# opaq_n1.net
KiCad netlist of a schematic drawn in EAGLE
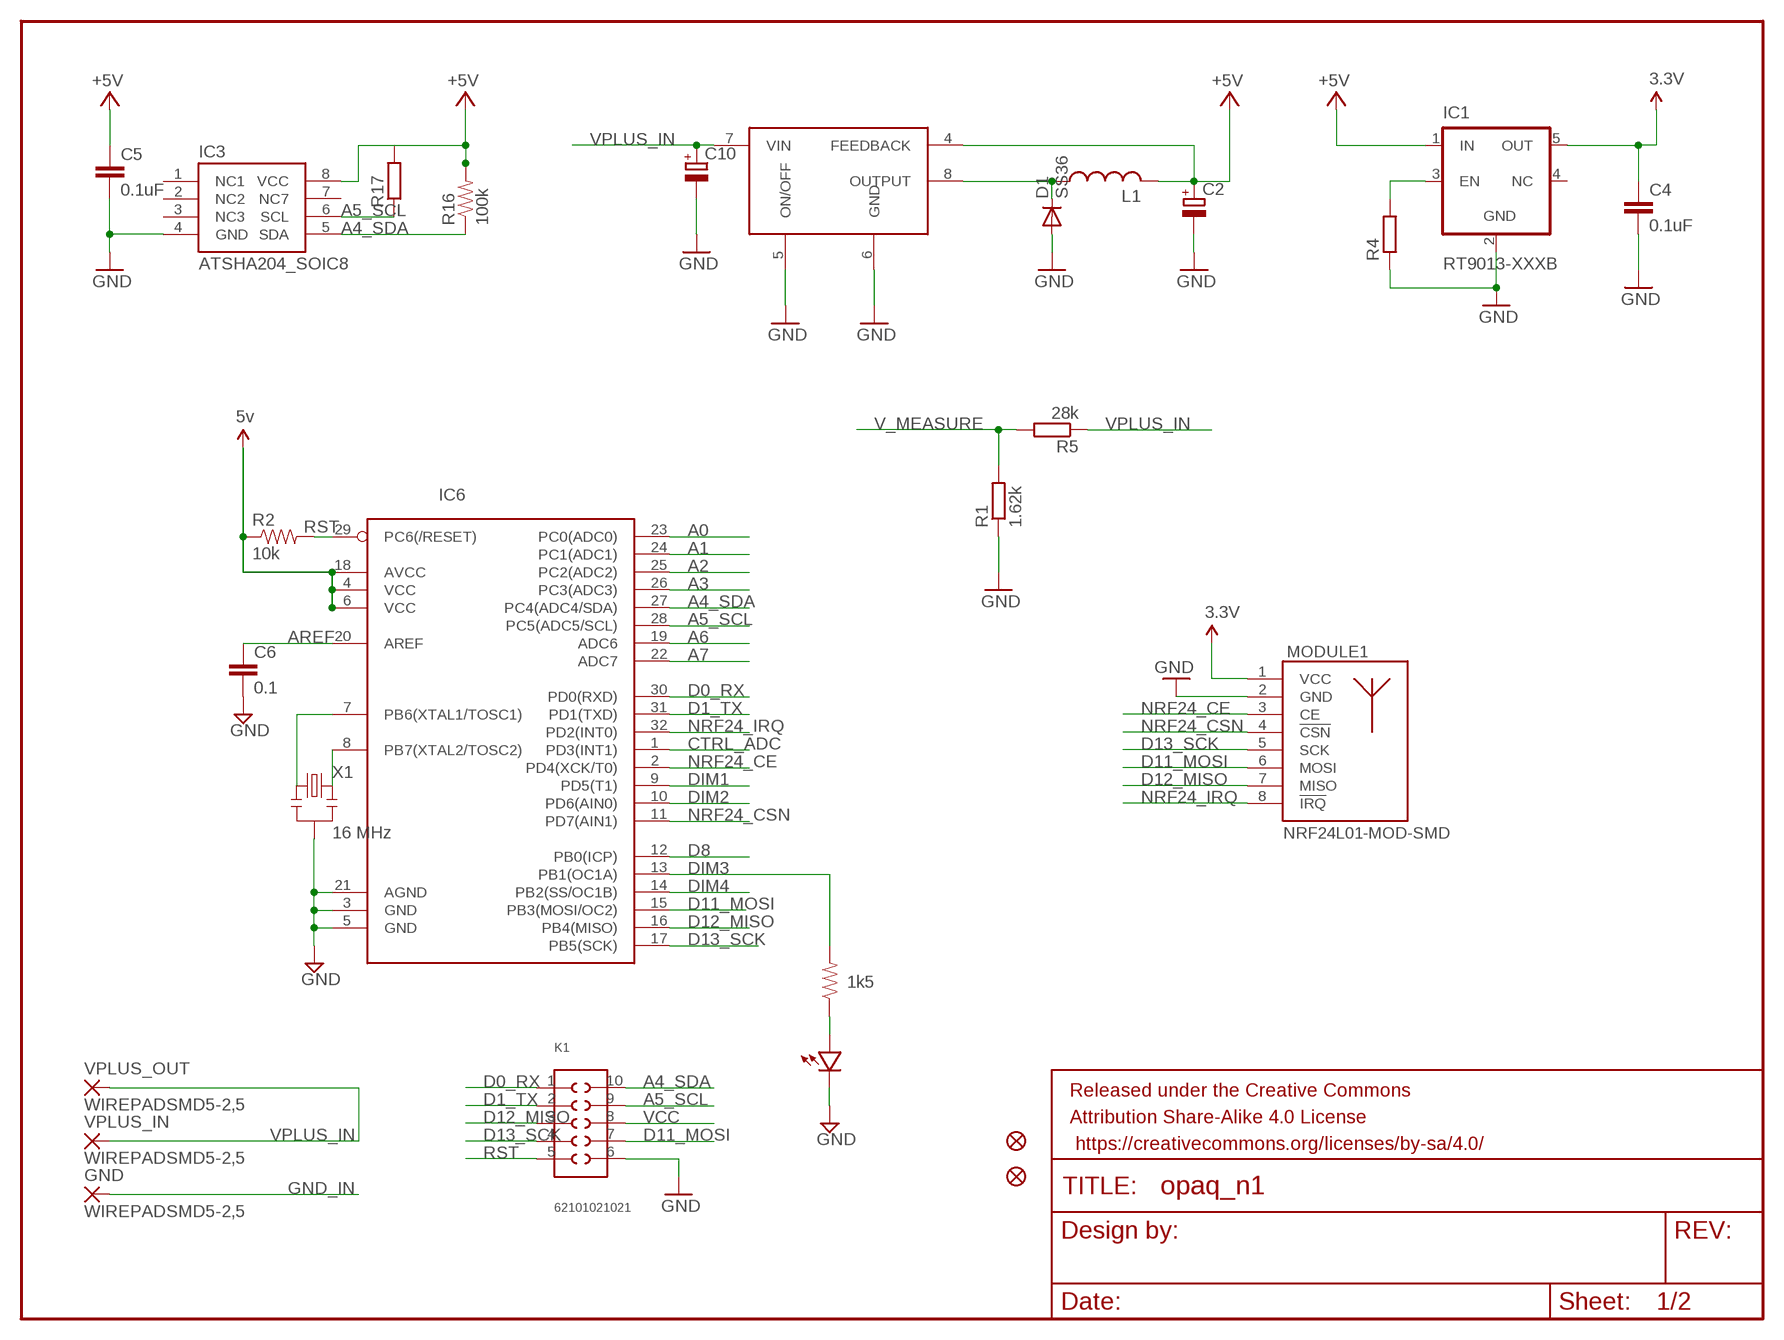
[diagram p0: schematic, sheet 1]
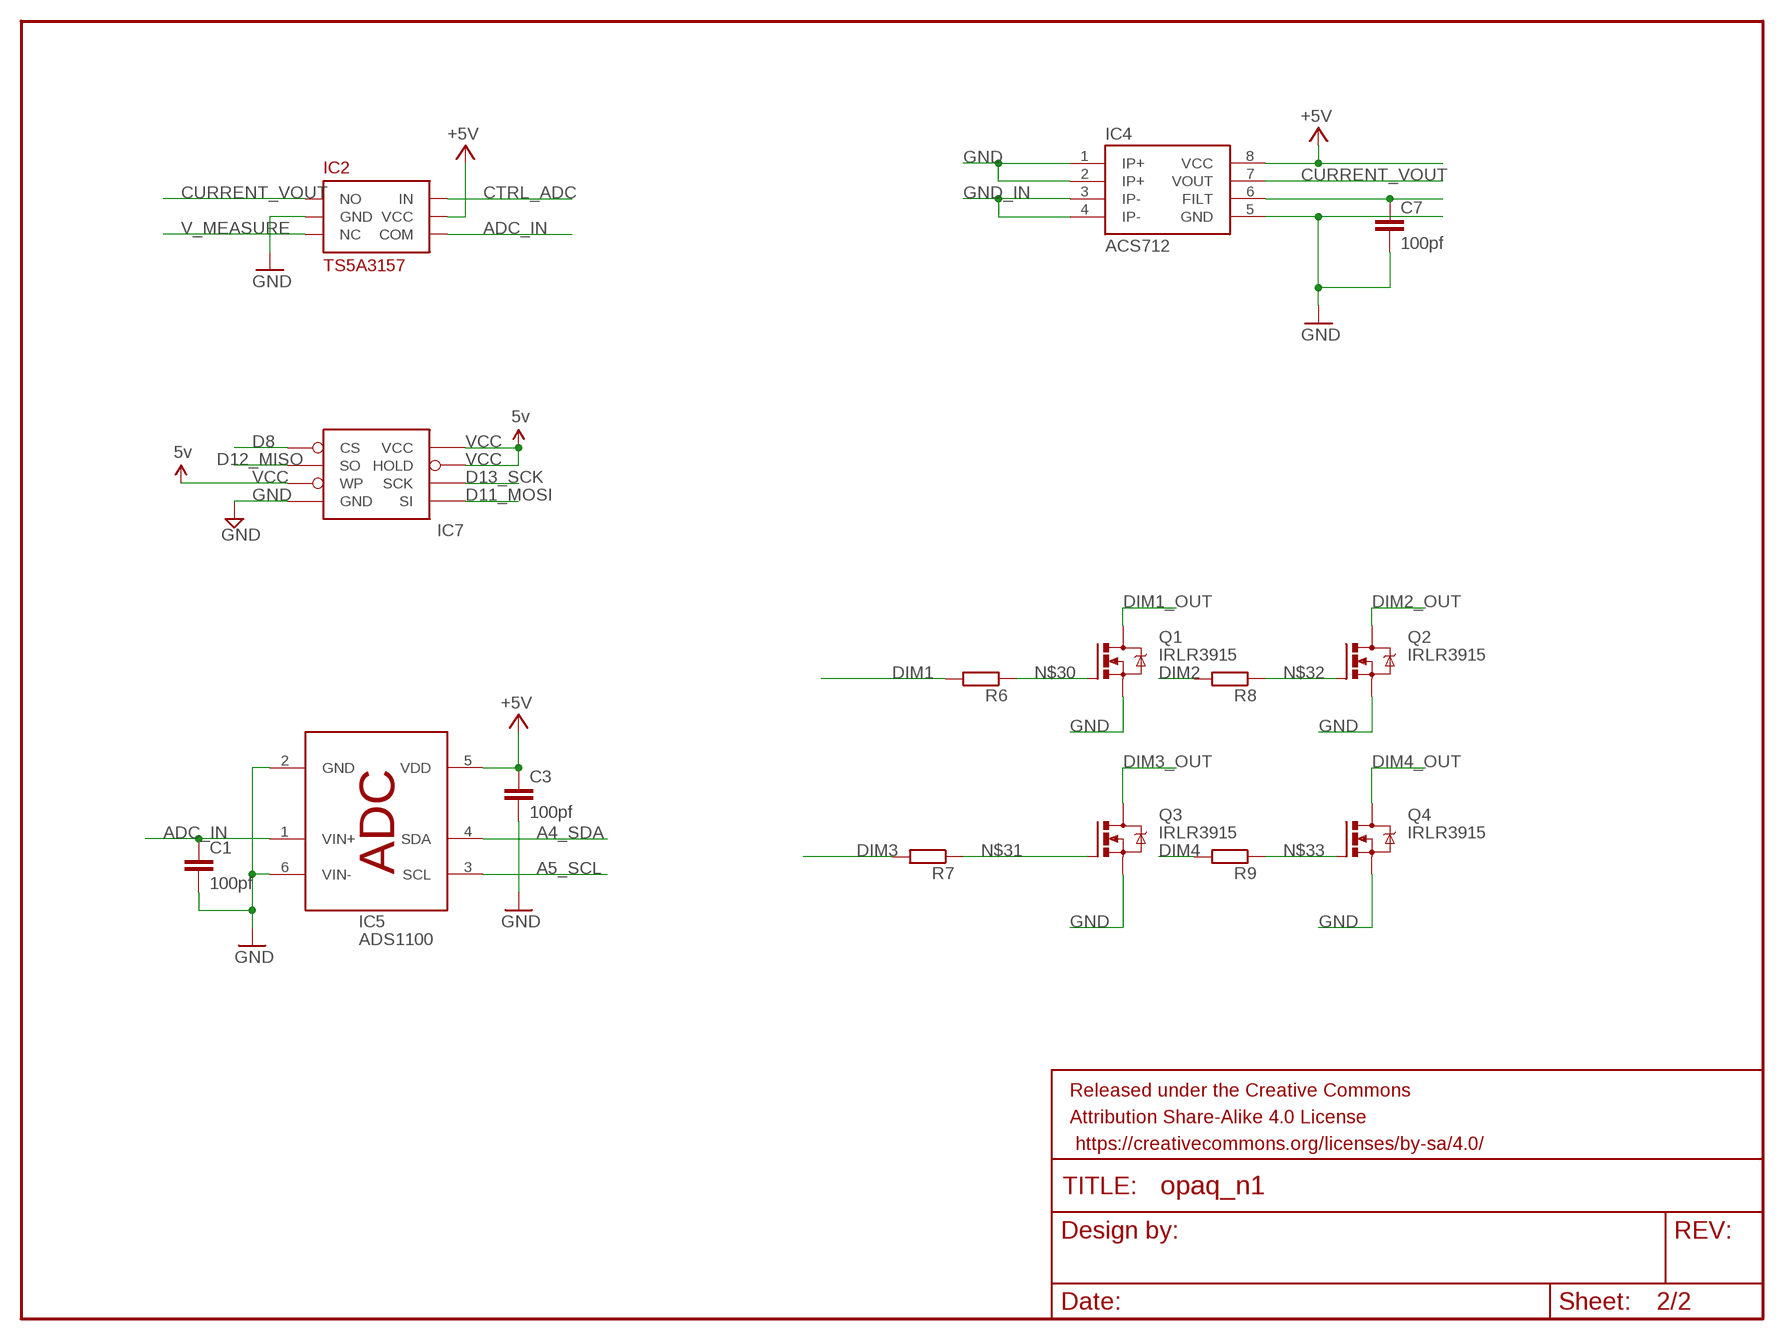
[diagram p1: schematic, sheet 2]

(export (version "E")
  (design (tool "Eeschema 10.0.6"))
  (components
    (comp (ref "C2")
      (value "CPOL-EUC/6032-28R")
      (footprint "eagle-import:C_6032-28R")
      (libsource (lib "eagle-import") (part "CPOL-EUC/6032-28R"))
    )
    (comp (ref "C4")
      (value "0.1uF")
      (footprint "eagle-import:0805")
      (libsource (lib "eagle-import") (part "SparkFun-Passives_CAP0805"))
    )
    (comp (ref "C5")
      (value "0.1uF")
      (footprint "eagle-import:0805")
      (libsource (lib "eagle-import") (part "SparkFun-Passives_CAP0805"))
    )
    (comp (ref "C6")
      (value "0.1")
      (footprint "eagle-import:0603-CAP")
      (libsource (lib "eagle-import") (part "CAP0603-CAP"))
    )
    (comp (ref "C10")
      (value "CPOL-EUD/7343-31R")
      (footprint "eagle-import:D_7343-31R")
      (libsource (lib "eagle-import") (part "CPOL-EUD/7343-31R"))
    )
    (comp (ref "D1")
      (value "SS36")
      (footprint "eagle-import:SMA-DIODE")
      (libsource (lib "eagle-import") (part "DIODESMA"))
    )
    (comp (ref "DIM")
      (value "LED0603")
      (footprint "eagle-import:0603-LED")
      (libsource (lib "eagle-import") (part "LED0603"))
    )
    (comp (ref "FRAME1")
      (value "FRAME-LETTER")
      (footprint "eagle-import:CREATIVE_COMMONS")
      (libsource (lib "eagle-import") (part "FRAME-LETTER"))
    )
    (comp (ref "GND")
      (value "WIREPADSMD5-2,5")
      (footprint "eagle-import:5-2,5")
      (libsource (lib "eagle-import") (part "WIREPADSMD5-2,5"))
    )
    (comp (ref "IC1")
      (value "RT9013-XXXB")
      (footprint "eagle-import:SOT23-5")
      (libsource (lib "eagle-import") (part "RT9013-XXXB"))
    )
    (comp (ref "IC3")
      (value "ATSHA204_SOIC8")
      (footprint "eagle-import:SOIC8")
      (libsource (lib "eagle-import") (part "ATSHA204_SOIC8"))
    )
    (comp (ref "IC6")
      (value "ATMega-328")
      (footprint "eagle-import:MLF32")
      (libsource (lib "eagle-import") (part "ATMEGA168/328MLF"))
    )
    (comp (ref "IC8")
      (value "LM2594HV")
      (footprint "eagle-import:SO08")
      (libsource (lib "eagle-import") (part "LM2594"))
    )
    (comp (ref "JP1")
      (value "FIDUCIAL1X2.5")
      (footprint "eagle-import:FIDUCIAL-1X2.5")
      (libsource (lib "eagle-import") (part "FIDUCIAL1X2.5"))
    )
    (comp (ref "JP2")
      (value "FIDUCIAL1X2.5")
      (footprint "eagle-import:FIDUCIAL-1X2.5")
      (libsource (lib "eagle-import") (part "FIDUCIAL1X2.5"))
    )
    (comp (ref "K1")
      (value "62101021021")
      (footprint "eagle-import:62101021021")
      (libsource (lib "eagle-import") (part "62101021021"))
    )
    (comp (ref "L1")
      (value "NR6045")
      (footprint "eagle-import:2525")
      (libsource (lib "eagle-import") (part "NR6045"))
    )
    (comp (ref "MODULE1")
      (value "NRF24L01-MOD-SMD")
      (footprint "eagle-import:SMD8-MODULE")
      (libsource (lib "eagle-import") (part "NRF24L01-MOD-SMD"))
    )
    (comp (ref "R1")
      (value "1.62k")
      (footprint "eagle-import:0805")
      (libsource (lib "eagle-import") (part "R-EU_R0805"))
    )
    (comp (ref "R2")
      (value "10k")
      (footprint "eagle-import:0603-RES")
      (libsource (lib "eagle-import") (part "RESISTOR0603-RES"))
    )
    (comp (ref "R3")
      (value "1k5")
      (footprint "eagle-import:0603-RES")
      (libsource (lib "eagle-import") (part "RESISTOR0603-RES"))
    )
    (comp (ref "R4")
      (value "R-EU_R0805")
      (footprint "eagle-import:0805")
      (libsource (lib "eagle-import") (part "R-EU_R0805"))
    )
    (comp (ref "R5")
      (value "28k")
      (footprint "eagle-import:0805")
      (libsource (lib "eagle-import") (part "R-EU_R0805"))
    )
    (comp (ref "R16")
      (value "100k")
      (footprint "eagle-import:0805")
      (libsource (lib "eagle-import") (part "SparkFun-Passives_RESISTOR0805-RES"))
    )
    (comp (ref "R17")
      (value "R-EU_R0805")
      (footprint "eagle-import:0805")
      (libsource (lib "eagle-import") (part "R-EU_R0805"))
    )
    (comp (ref "VPLUS_IN")
      (value "WIREPADSMD5-2,5")
      (footprint "eagle-import:5-2,5")
      (libsource (lib "eagle-import") (part "WIREPADSMD5-2,5"))
    )
    (comp (ref "VPLUS_OUT")
      (value "WIREPADSMD5-2,5")
      (footprint "eagle-import:5-2,5")
      (libsource (lib "eagle-import") (part "WIREPADSMD5-2,5"))
    )
    (comp (ref "X1")
      (value "16 MHz")
      (footprint "eagle-import:RESONATOR-SMD")
      (libsource (lib "eagle-import") (part "RESONATORSMD"))
    )
    (comp (ref "C1")
      (value "100pf")
      (footprint "eagle-import:0402-CAP")
      (libsource (lib "eagle-import") (part "SparkFun-Passives_CAP0402-CAP"))
    )
    (comp (ref "C3")
      (value "100pf")
      (footprint "eagle-import:0402-CAP")
      (libsource (lib "eagle-import") (part "SparkFun-Passives_CAP0402-CAP"))
    )
    (comp (ref "C7")
      (value "100pf")
      (footprint "eagle-import:0402-CAP")
      (libsource (lib "eagle-import") (part "SparkFun-Passives_CAP0402-CAP"))
    )
    (comp (ref "FRAME2")
      (value "FRAME-LETTERNO_PACKAGE")
      (footprint "eagle-import:DUMMY")
      (fields (field (name "DESIGNER") "Nobody"))
      (libsource (lib "eagle-import") (part "FRAME-LETTERNO_PACKAGE"))
    )
    (comp (ref "IC2")
      (value "TS5A3157")
      (footprint "eagle-import:SOT23-6")
      (libsource (lib "eagle-import") (part "TS5A3157"))
    )
    (comp (ref "IC4")
      (value "ACS712")
      (footprint "eagle-import:SO08")
      (libsource (lib "eagle-import") (part "ACS712"))
    )
    (comp (ref "IC5")
      (value "ADS1100")
      (footprint "eagle-import:SOT23-6")
      (fields (field (name "MF") "TI"))
      (libsource (lib "eagle-import") (part "ADS1100"))
    )
    (comp (ref "IC7")
      (value "AT25F512BWIDE_5.3MM")
      (footprint "eagle-import:SO08WIDE")
      (libsource (lib "eagle-import") (part "AT25F512BWIDE_5.3MM"))
    )
    (comp (ref "Q1")
      (value "IRLR3915")
      (footprint "eagle-import:D-PAK_TO252AA")
      (libsource (lib "eagle-import") (part "IRLR3915"))
    )
    (comp (ref "Q2")
      (value "IRLR3915")
      (footprint "eagle-import:D-PAK_TO252AA")
      (libsource (lib "eagle-import") (part "IRLR3915"))
    )
    (comp (ref "Q3")
      (value "IRLR3915")
      (footprint "eagle-import:D-PAK_TO252AA")
      (libsource (lib "eagle-import") (part "IRLR3915"))
    )
    (comp (ref "Q4")
      (value "IRLR3915")
      (footprint "eagle-import:D-PAK_TO252AA")
      (libsource (lib "eagle-import") (part "IRLR3915"))
    )
    (comp (ref "R6")
      (value "R-EU_R0805")
      (footprint "eagle-import:0805")
      (libsource (lib "eagle-import") (part "R-EU_R0805"))
    )
    (comp (ref "R7")
      (value "R-EU_R0805")
      (footprint "eagle-import:0805")
      (libsource (lib "eagle-import") (part "R-EU_R0805"))
    )
    (comp (ref "R8")
      (value "R-EU_R0805")
      (footprint "eagle-import:0805")
      (libsource (lib "eagle-import") (part "R-EU_R0805"))
    )
    (comp (ref "R9")
      (value "R-EU_R0805")
      (footprint "eagle-import:0805")
      (libsource (lib "eagle-import") (part "R-EU_R0805"))
    )
  )
  (nets
    (net (code "1") (name "+5V") (class "Default")
      (node (ref "C2") (pin "+") (pinfunction "+_+") (pintype "passive"))
      (node (ref "C3") (pin "1") (pinfunction "1_1") (pintype "passive"))
      (node (ref "C5") (pin "1") (pinfunction "1_1") (pintype "passive"))
      (node (ref "IC1") (pin "1") (pinfunction "IN_1") (pintype "input"))
      (node (ref "IC2") (pin "5") (pinfunction "VCC_5") (pintype "bidirectional"))
      (node (ref "IC3") (pin "8") (pinfunction "VCC_8") (pintype "power_in"))
      (node (ref "IC4") (pin "8") (pinfunction "VCC_8") (pintype "bidirectional"))
      (node (ref "IC5") (pin "5") (pinfunction "VDD_5") (pintype "power_in"))
      (node (ref "IC8") (pin "4") (pinfunction "FEEDBACK_4") (pintype "bidirectional"))
      (node (ref "L1") (pin "P$1") (pinfunction "P$1_P$1") (pintype "passive"))
      (node (ref "R16") (pin "2") (pinfunction "2_2") (pintype "passive"))
      (node (ref "R17") (pin "2") (pinfunction "2_2") (pintype "passive"))
    )
    (net (code "2") (name "3.3V") (class "Default")
      (node (ref "C4") (pin "1") (pinfunction "1_1") (pintype "passive"))
      (node (ref "IC1") (pin "5") (pinfunction "OUT_5") (pintype "passive"))
      (node (ref "MODULE1") (pin "1") (pinfunction "VCC_1") (pintype "power_in"))
    )
    (net (code "3") (name "A0") (class "Default")
      (node (ref "IC6") (pin "23") (pinfunction "PC0(ADC0)_23") (pintype "bidirectional"))
    )
    (net (code "4") (name "A1") (class "Default")
      (node (ref "IC6") (pin "24") (pinfunction "PC1(ADC1)_24") (pintype "bidirectional"))
    )
    (net (code "5") (name "A2") (class "Default")
      (node (ref "IC6") (pin "25") (pinfunction "PC2(ADC2)_25") (pintype "bidirectional"))
    )
    (net (code "6") (name "A3") (class "Default")
      (node (ref "IC6") (pin "26") (pinfunction "PC3(ADC3)_26") (pintype "bidirectional"))
    )
    (net (code "7") (name "A4_SDA") (class "Default")
      (node (ref "IC3") (pin "5") (pinfunction "SDA_5") (pintype "bidirectional"))
      (node (ref "IC5") (pin "4") (pinfunction "SDA_4") (pintype "bidirectional"))
      (node (ref "IC6") (pin "27") (pinfunction "PC4(ADC4/SDA)_27") (pintype "bidirectional"))
      (node (ref "K1") (pin "10") (pinfunction "10_10") (pintype "passive"))
      (node (ref "R16") (pin "1") (pinfunction "1_1") (pintype "passive"))
    )
    (net (code "8") (name "A5_SCL") (class "Default")
      (node (ref "IC3") (pin "6") (pinfunction "SCL_6") (pintype "bidirectional"))
      (node (ref "IC5") (pin "3") (pinfunction "SCL_3") (pintype "input"))
      (node (ref "IC6") (pin "28") (pinfunction "PC5(ADC5/SCL)_28") (pintype "bidirectional"))
      (node (ref "K1") (pin "9") (pinfunction "9_9") (pintype "passive"))
      (node (ref "R17") (pin "1") (pinfunction "1_1") (pintype "passive"))
    )
    (net (code "9") (name "A6") (class "Default")
      (node (ref "IC6") (pin "19") (pinfunction "ADC6_19") (pintype "bidirectional"))
    )
    (net (code "10") (name "A7") (class "Default")
      (node (ref "IC6") (pin "22") (pinfunction "ADC7_22") (pintype "bidirectional"))
    )
    (net (code "11") (name "ADC_IN") (class "Default")
      (node (ref "C1") (pin "1") (pinfunction "1_1") (pintype "passive"))
      (node (ref "IC2") (pin "4") (pinfunction "COM_4") (pintype "bidirectional"))
      (node (ref "IC5") (pin "1") (pinfunction "VIN+_1") (pintype "input"))
    )
    (net (code "12") (name "AREF") (class "Default")
      (node (ref "C6") (pin "1") (pinfunction "1_1") (pintype "passive"))
      (node (ref "IC6") (pin "20") (pinfunction "AREF_20") (pintype "bidirectional"))
    )
    (net (code "13") (name "CTRL_ADC") (class "Default")
      (node (ref "IC2") (pin "6") (pinfunction "IN_6") (pintype "bidirectional"))
      (node (ref "IC6") (pin "1") (pinfunction "PD3(INT1)_1") (pintype "bidirectional"))
    )
    (net (code "14") (name "CURRENT_VOUT") (class "Default")
      (node (ref "IC2") (pin "1") (pinfunction "NO_1") (pintype "bidirectional"))
      (node (ref "IC4") (pin "7") (pinfunction "VOUT_7") (pintype "bidirectional"))
    )
    (net (code "15") (name "D0_RX") (class "Default")
      (node (ref "IC6") (pin "30") (pinfunction "PD0(RXD)_30") (pintype "bidirectional"))
      (node (ref "K1") (pin "1") (pinfunction "1_1") (pintype "passive"))
    )
    (net (code "16") (name "D1_TX") (class "Default")
      (node (ref "IC6") (pin "31") (pinfunction "PD1(TXD)_31") (pintype "bidirectional"))
      (node (ref "K1") (pin "2") (pinfunction "2_2") (pintype "passive"))
    )
    (net (code "17") (name "D8") (class "Default")
      (node (ref "IC6") (pin "12") (pinfunction "PB0(ICP)_12") (pintype "bidirectional"))
      (node (ref "IC7") (pin "1") (pinfunction "CS_1") (pintype "bidirectional"))
    )
    (net (code "18") (name "D11_MOSI") (class "Default")
      (node (ref "IC6") (pin "15") (pinfunction "PB3(MOSI/OC2)_15") (pintype "bidirectional"))
      (node (ref "IC7") (pin "5") (pinfunction "SI_5") (pintype "bidirectional"))
      (node (ref "K1") (pin "7") (pinfunction "7_7") (pintype "passive"))
      (node (ref "MODULE1") (pin "6") (pinfunction "MOSI_6") (pintype "input"))
    )
    (net (code "19") (name "D12_MISO") (class "Default")
      (node (ref "IC6") (pin "16") (pinfunction "PB4(MISO)_16") (pintype "bidirectional"))
      (node (ref "IC7") (pin "2") (pinfunction "SO_2") (pintype "bidirectional"))
      (node (ref "K1") (pin "3") (pinfunction "3_3") (pintype "passive"))
      (node (ref "MODULE1") (pin "7") (pinfunction "MISO_7") (pintype "output"))
    )
    (net (code "20") (name "D13_SCK") (class "Default")
      (node (ref "IC6") (pin "17") (pinfunction "PB5(SCK)_17") (pintype "bidirectional"))
      (node (ref "IC7") (pin "6") (pinfunction "SCK_6") (pintype "bidirectional"))
      (node (ref "K1") (pin "4") (pinfunction "4_4") (pintype "passive"))
      (node (ref "MODULE1") (pin "5") (pinfunction "SCK_5") (pintype "input"))
    )
    (net (code "21") (name "DIM1") (class "Default")
      (node (ref "IC6") (pin "9") (pinfunction "PD5(T1)_9") (pintype "bidirectional"))
      (node (ref "R6") (pin "2") (pinfunction "2_2") (pintype "passive"))
    )
    (net (code "22") (name "DIM1_OUT") (class "Default")
      (node (ref "Q1") (pin "4") (pinfunction "D_4") (pintype "passive"))
    )
    (net (code "23") (name "DIM2") (class "Default")
      (node (ref "IC6") (pin "10") (pinfunction "PD6(AIN0)_10") (pintype "bidirectional"))
      (node (ref "R8") (pin "2") (pinfunction "2_2") (pintype "passive"))
    )
    (net (code "24") (name "DIM2_OUT") (class "Default")
      (node (ref "Q2") (pin "4") (pinfunction "D_4") (pintype "passive"))
    )
    (net (code "25") (name "DIM3") (class "Default")
      (node (ref "IC6") (pin "13") (pinfunction "PB1(OC1A)_13") (pintype "bidirectional"))
      (node (ref "R3") (pin "2") (pinfunction "2_2") (pintype "passive"))
      (node (ref "R7") (pin "2") (pinfunction "2_2") (pintype "passive"))
    )
    (net (code "26") (name "DIM3_OUT") (class "Default")
      (node (ref "Q3") (pin "4") (pinfunction "D_4") (pintype "passive"))
    )
    (net (code "27") (name "DIM4") (class "Default")
      (node (ref "IC6") (pin "14") (pinfunction "PB2(SS/OC1B)_14") (pintype "bidirectional"))
      (node (ref "R9") (pin "2") (pinfunction "2_2") (pintype "passive"))
    )
    (net (code "28") (name "DIM4_OUT") (class "Default")
      (node (ref "Q4") (pin "4") (pinfunction "D_4") (pintype "passive"))
    )
    (net (code "29") (name "GND") (class "Default")
      (node (ref "C1") (pin "2") (pinfunction "2_2") (pintype "passive"))
      (node (ref "C10") (pin "-") (pinfunction "-_-") (pintype "passive"))
      (node (ref "C2") (pin "-") (pinfunction "-_-") (pintype "passive"))
      (node (ref "C3") (pin "2") (pinfunction "2_2") (pintype "passive"))
      (node (ref "C4") (pin "2") (pinfunction "2_2") (pintype "passive"))
      (node (ref "C5") (pin "2") (pinfunction "2_2") (pintype "passive"))
      (node (ref "C6") (pin "2") (pinfunction "2_2") (pintype "passive"))
      (node (ref "C7") (pin "2") (pinfunction "2_2") (pintype "passive"))
      (node (ref "D1") (pin "A") (pinfunction "A_A") (pintype "passive"))
      (node (ref "DIM") (pin "MINUS") (pinfunction "MINUS_MINUS") (pintype "passive"))
      (node (ref "IC1") (pin "2") (pinfunction "GND_2") (pintype "power_in"))
      (node (ref "IC2") (pin "2") (pinfunction "GND_2") (pintype "bidirectional"))
      (node (ref "IC3") (pin "4") (pinfunction "GND_4") (pintype "power_in"))
      (node (ref "IC4") (pin "1") (pinfunction "IP+_1") (pintype "bidirectional"))
      (node (ref "IC4") (pin "2") (pinfunction "IP+_2") (pintype "bidirectional"))
      (node (ref "IC4") (pin "5") (pinfunction "GND_5") (pintype "bidirectional"))
      (node (ref "IC5") (pin "2") (pinfunction "GND_2") (pintype "power_in"))
      (node (ref "IC5") (pin "6") (pinfunction "VIN-_6") (pintype "input"))
      (node (ref "IC6") (pin "21") (pinfunction "AGND_21") (pintype "bidirectional"))
      (node (ref "IC6") (pin "3") (pinfunction "GND_3") (pintype "bidirectional"))
      (node (ref "IC6") (pin "5") (pinfunction "GND_5") (pintype "bidirectional"))
      (node (ref "IC7") (pin "4") (pinfunction "GND_4") (pintype "bidirectional"))
      (node (ref "IC8") (pin "5") (pinfunction "ON/OFF_5") (pintype "bidirectional"))
      (node (ref "IC8") (pin "6") (pinfunction "GND_6") (pintype "bidirectional"))
      (node (ref "K1") (pin "6") (pinfunction "6_6") (pintype "passive"))
      (node (ref "MODULE1") (pin "2") (pinfunction "GND_2") (pintype "power_in"))
      (node (ref "Q1") (pin "3") (pinfunction "S_3") (pintype "passive"))
      (node (ref "Q2") (pin "3") (pinfunction "S_3") (pintype "passive"))
      (node (ref "Q3") (pin "3") (pinfunction "S_3") (pintype "passive"))
      (node (ref "Q4") (pin "3") (pinfunction "S_3") (pintype "passive"))
      (node (ref "R1") (pin "1") (pinfunction "1_1") (pintype "passive"))
      (node (ref "R4") (pin "1") (pinfunction "1_1") (pintype "passive"))
      (node (ref "X1") (pin "2") (pinfunction "2_2") (pintype "passive"))
    )
    (net (code "30") (name "GND_IN") (class "Default")
      (node (ref "GND") (pin "1") (pinfunction "P_1") (pintype "passive"))
      (node (ref "IC4") (pin "3") (pinfunction "IP-_3") (pintype "bidirectional"))
      (node (ref "IC4") (pin "4") (pinfunction "IP-_4") (pintype "bidirectional"))
    )
    (net (code "31") (name "N$30") (class "Default")
      (node (ref "Q1") (pin "1") (pinfunction "G_1") (pintype "passive"))
      (node (ref "R6") (pin "1") (pinfunction "1_1") (pintype "passive"))
    )
    (net (code "32") (name "N$31") (class "Default")
      (node (ref "Q3") (pin "1") (pinfunction "G_1") (pintype "passive"))
      (node (ref "R7") (pin "1") (pinfunction "1_1") (pintype "passive"))
    )
    (net (code "33") (name "N$32") (class "Default")
      (node (ref "Q2") (pin "1") (pinfunction "G_1") (pintype "passive"))
      (node (ref "R8") (pin "1") (pinfunction "1_1") (pintype "passive"))
    )
    (net (code "34") (name "N$33") (class "Default")
      (node (ref "Q4") (pin "1") (pinfunction "G_1") (pintype "passive"))
      (node (ref "R9") (pin "1") (pinfunction "1_1") (pintype "passive"))
    )
    (net (code "35") (name "NRF24_CE") (class "Default")
      (node (ref "IC6") (pin "2") (pinfunction "PD4(XCK/T0)_2") (pintype "bidirectional"))
      (node (ref "MODULE1") (pin "3") (pinfunction "CE_3") (pintype "input"))
    )
    (net (code "36") (name "NRF24_CSN") (class "Default")
      (node (ref "IC6") (pin "11") (pinfunction "PD7(AIN1)_11") (pintype "bidirectional"))
      (node (ref "MODULE1") (pin "4") (pinfunction "~{CSN}_4") (pintype "input"))
    )
    (net (code "37") (name "NRF24_IRQ") (class "Default")
      (node (ref "IC6") (pin "32") (pinfunction "PD2(INT0)_32") (pintype "bidirectional"))
      (node (ref "MODULE1") (pin "8") (pinfunction "~{IRQ}_8") (pintype "open_collector"))
    )
    (net (code "38") (name "Net-(DIM-PadPLUS)") (class "Default")
      (node (ref "DIM") (pin "PLUS") (pinfunction "PLUS_PLUS") (pintype "passive"))
      (node (ref "R3") (pin "1") (pinfunction "1_1") (pintype "passive"))
    )
    (net (code "39") (name "Net-(IC1-EN)") (class "Default")
      (node (ref "IC1") (pin "3") (pinfunction "EN_3") (pintype "input"))
      (node (ref "R4") (pin "2") (pinfunction "2_2") (pintype "passive"))
    )
    (net (code "40") (name "Net-(IC4-FILT)") (class "Default")
      (node (ref "C7") (pin "1") (pinfunction "1_1") (pintype "passive"))
      (node (ref "IC4") (pin "6") (pinfunction "FILT_6") (pintype "bidirectional"))
    )
    (net (code "41") (name "Net-(IC6-PB6(XTAL1{slash}TOSC1))") (class "Default")
      (node (ref "IC6") (pin "7") (pinfunction "PB6(XTAL1/TOSC1)_7") (pintype "bidirectional"))
      (node (ref "X1") (pin "1") (pinfunction "1_1") (pintype "passive"))
    )
    (net (code "42") (name "Net-(IC6-PB7(XTAL2{slash}TOSC2))") (class "Default")
      (node (ref "IC6") (pin "8") (pinfunction "PB7(XTAL2/TOSC2)_8") (pintype "bidirectional"))
      (node (ref "X1") (pin "3") (pinfunction "3_3") (pintype "passive"))
    )
    (net (code "43") (name "Net-(IC8-OUTPUT)") (class "Default")
      (node (ref "D1") (pin "C") (pinfunction "C_C") (pintype "passive"))
      (node (ref "IC8") (pin "8") (pinfunction "OUTPUT_8") (pintype "bidirectional"))
      (node (ref "L1") (pin "P$2") (pinfunction "P$2_P$2") (pintype "passive"))
    )
    (net (code "44") (name "RST") (class "Default")
      (node (ref "IC6") (pin "29") (pinfunction "PC6(/RESET)_29") (pintype "bidirectional"))
      (node (ref "K1") (pin "5") (pinfunction "5_5") (pintype "passive"))
      (node (ref "R2") (pin "2") (pinfunction "2_2") (pintype "passive"))
    )
    (net (code "45") (name "VCC") (class "Default")
      (node (ref "IC6") (pin "18") (pinfunction "AVCC_18") (pintype "bidirectional"))
      (node (ref "IC6") (pin "4") (pinfunction "VCC_4") (pintype "bidirectional"))
      (node (ref "IC6") (pin "6") (pinfunction "VCC_6") (pintype "bidirectional"))
      (node (ref "IC7") (pin "3") (pinfunction "WP_3") (pintype "bidirectional"))
      (node (ref "IC7") (pin "7") (pinfunction "HOLD_7") (pintype "bidirectional"))
      (node (ref "IC7") (pin "8") (pinfunction "VCC_8") (pintype "bidirectional"))
      (node (ref "K1") (pin "8") (pinfunction "8_8") (pintype "passive"))
      (node (ref "R2") (pin "1") (pinfunction "1_1") (pintype "passive"))
    )
    (net (code "46") (name "VPLUS_IN") (class "Default")
      (node (ref "C10") (pin "+") (pinfunction "+_+") (pintype "passive"))
      (node (ref "IC8") (pin "7") (pinfunction "VIN_7") (pintype "bidirectional"))
      (node (ref "R5") (pin "1") (pinfunction "1_1") (pintype "passive"))
      (node (ref "VPLUS_IN") (pin "1") (pinfunction "P_1") (pintype "passive"))
      (node (ref "VPLUS_OUT") (pin "1") (pinfunction "P_1") (pintype "passive"))
    )
    (net (code "47") (name "V_MEASURE") (class "Default")
      (node (ref "IC2") (pin "3") (pinfunction "NC_3") (pintype "bidirectional"))
      (node (ref "R1") (pin "2") (pinfunction "2_2") (pintype "passive"))
      (node (ref "R5") (pin "2") (pinfunction "2_2") (pintype "passive"))
    )
    (net (code "48") (name "unconnected-(IC1-NC-Pad4)") (class "Default")
      (node (ref "IC1") (pin "4") (pinfunction "NC_4") (pintype "no_connect"))
    )
    (net (code "49") (name "unconnected-(IC3-NC1-Pad1)") (class "Default")
      (node (ref "IC3") (pin "1") (pinfunction "NC1_1") (pintype "no_connect"))
    )
    (net (code "50") (name "unconnected-(IC3-NC2-Pad2)") (class "Default")
      (node (ref "IC3") (pin "2") (pinfunction "NC2_2") (pintype "no_connect"))
    )
    (net (code "51") (name "unconnected-(IC3-NC3-Pad3)") (class "Default")
      (node (ref "IC3") (pin "3") (pinfunction "NC3_3") (pintype "no_connect"))
    )
    (net (code "52") (name "unconnected-(IC3-NC7-Pad7)") (class "Default")
      (node (ref "IC3") (pin "7") (pinfunction "NC7_7") (pintype "no_connect"))
    )
  )
)
